# r_series.net
KiCad netlist of a schematic drawn in EAGLE
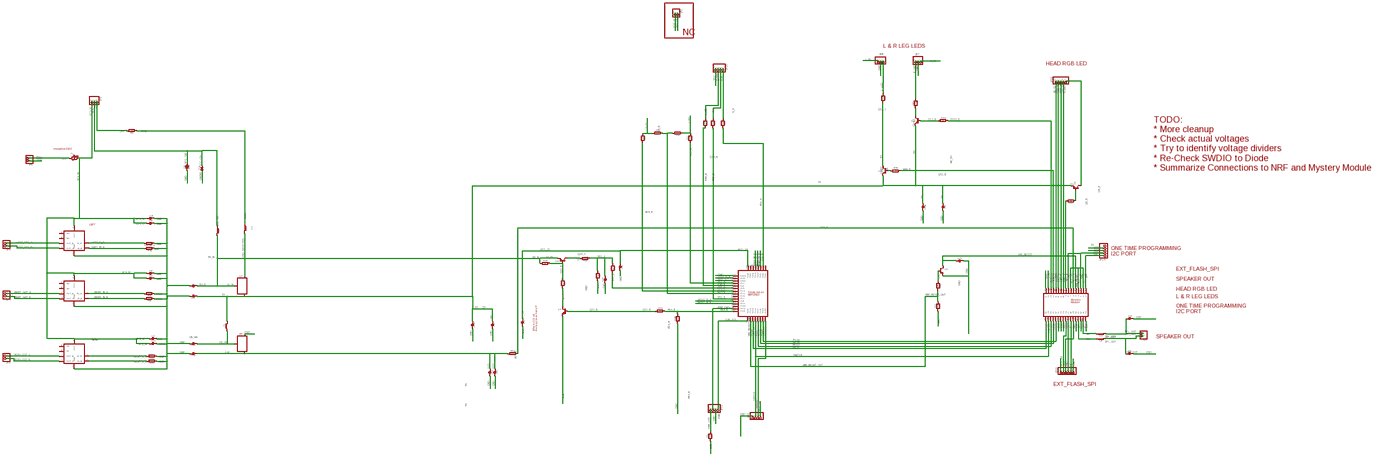
[diagram p0: schematic, sheet 1, overview]
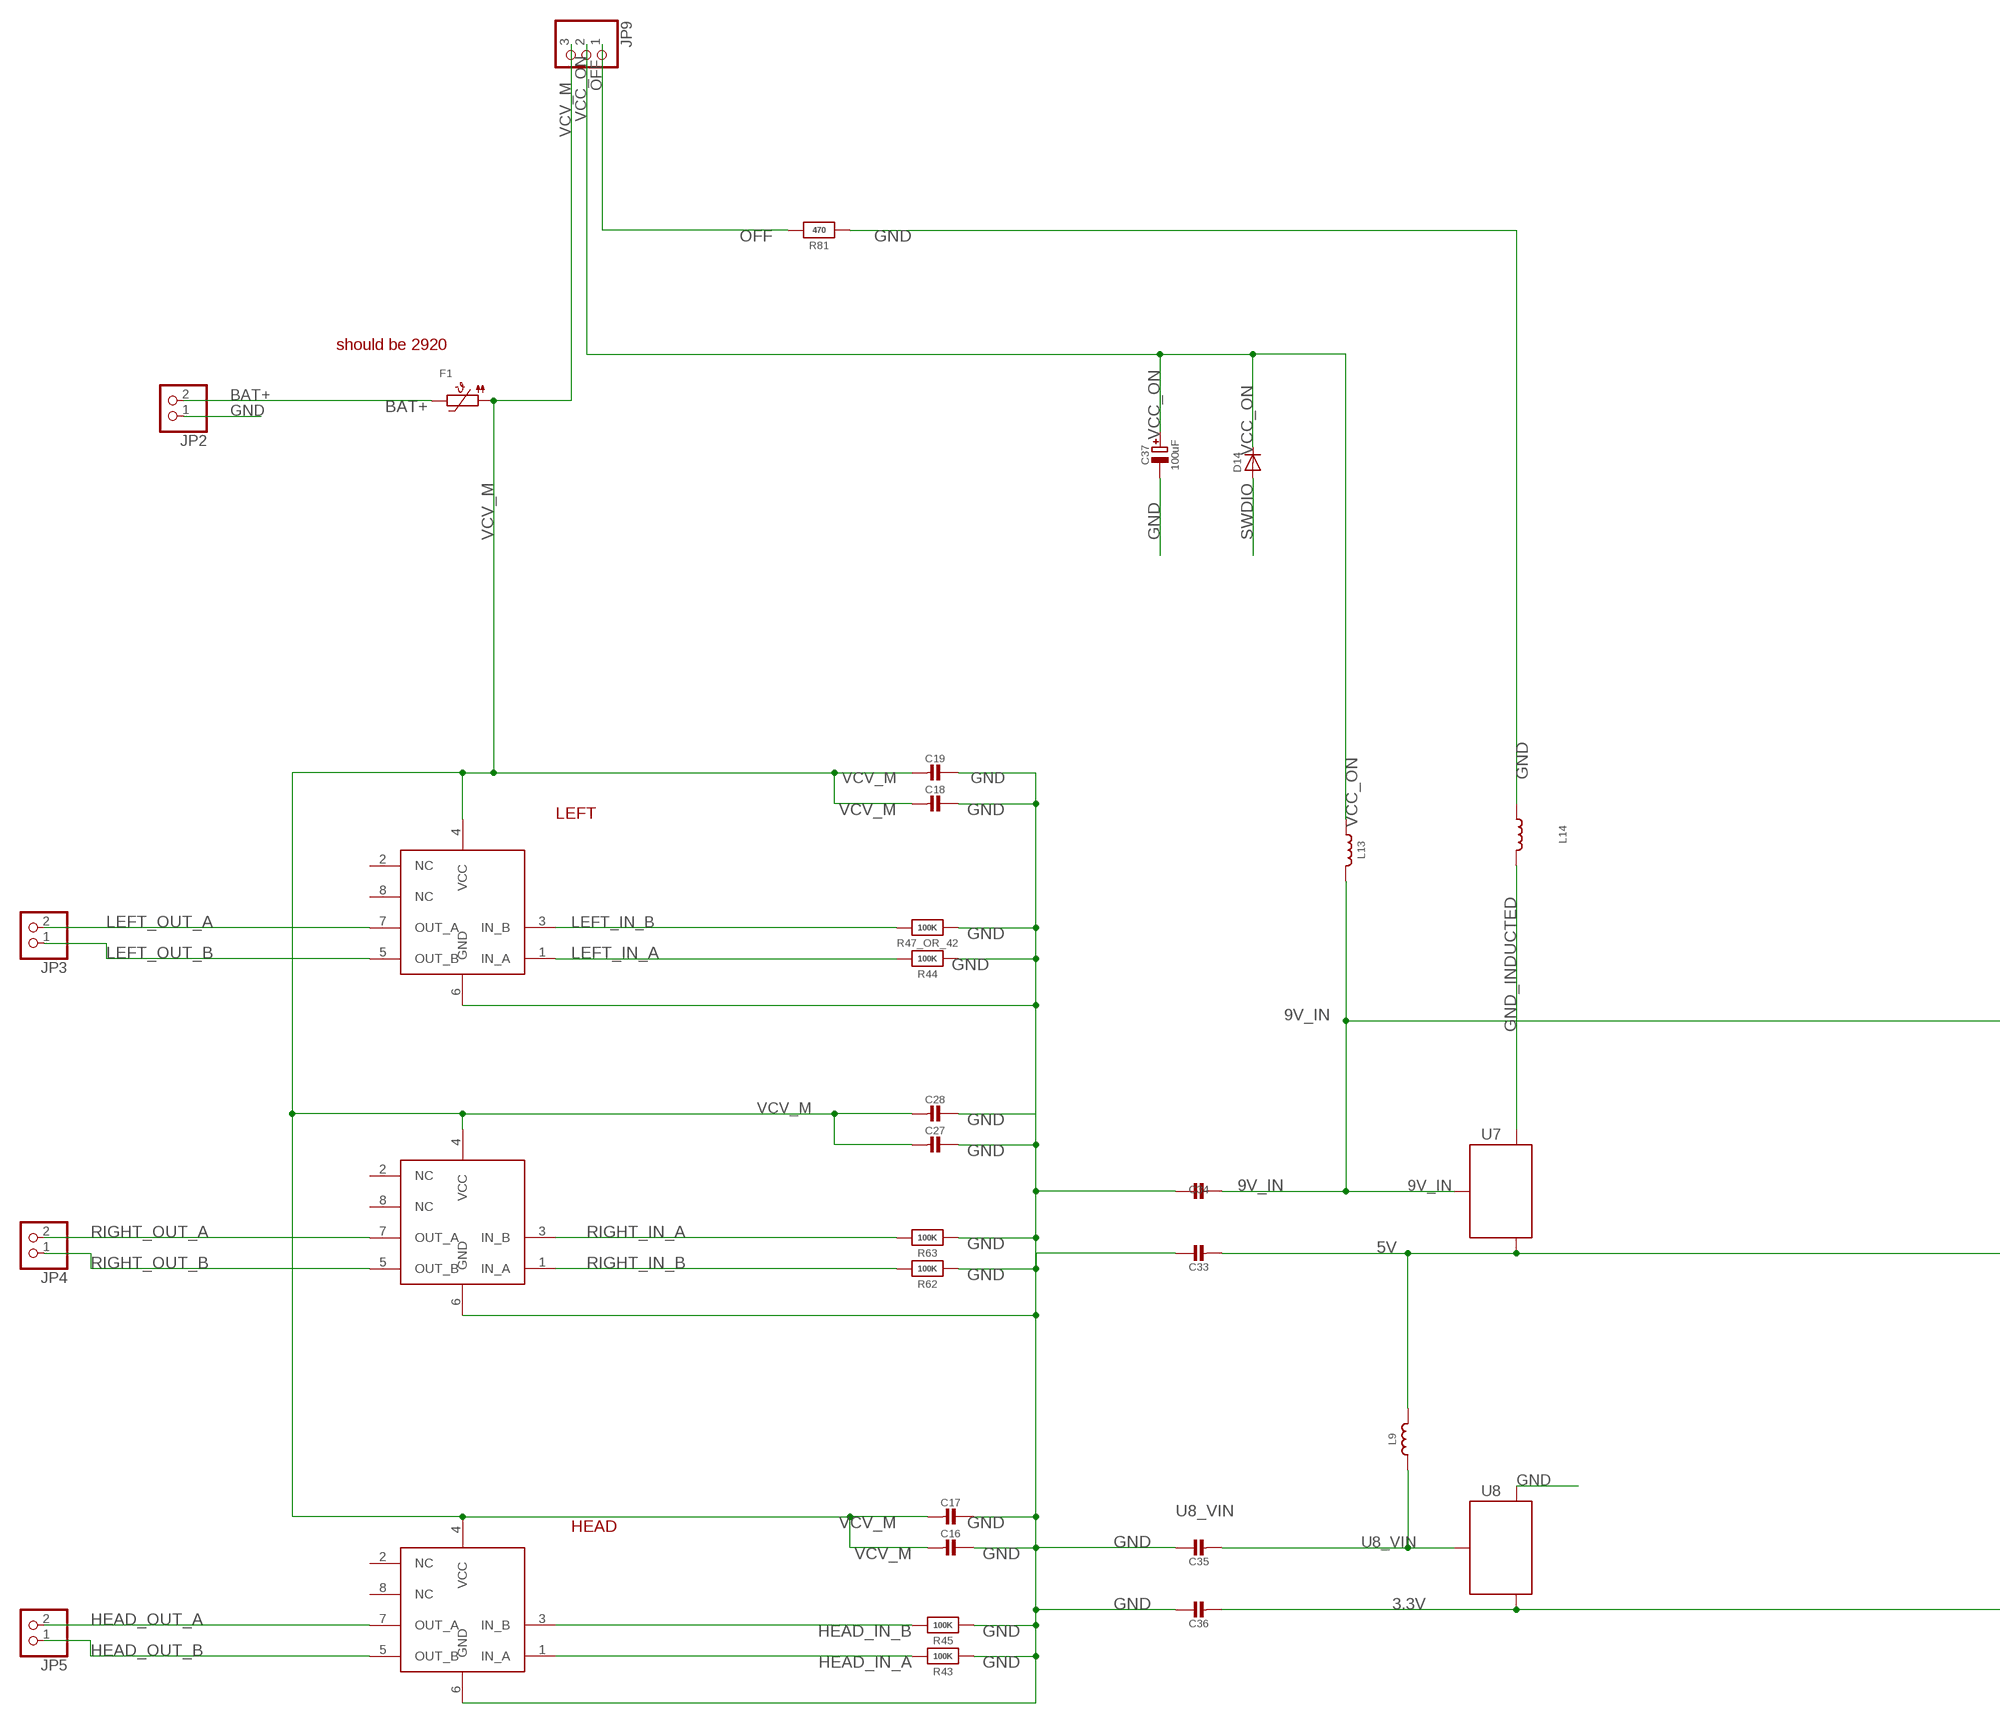
[diagram p1: schematic, sheet 1, part 1 of 4]
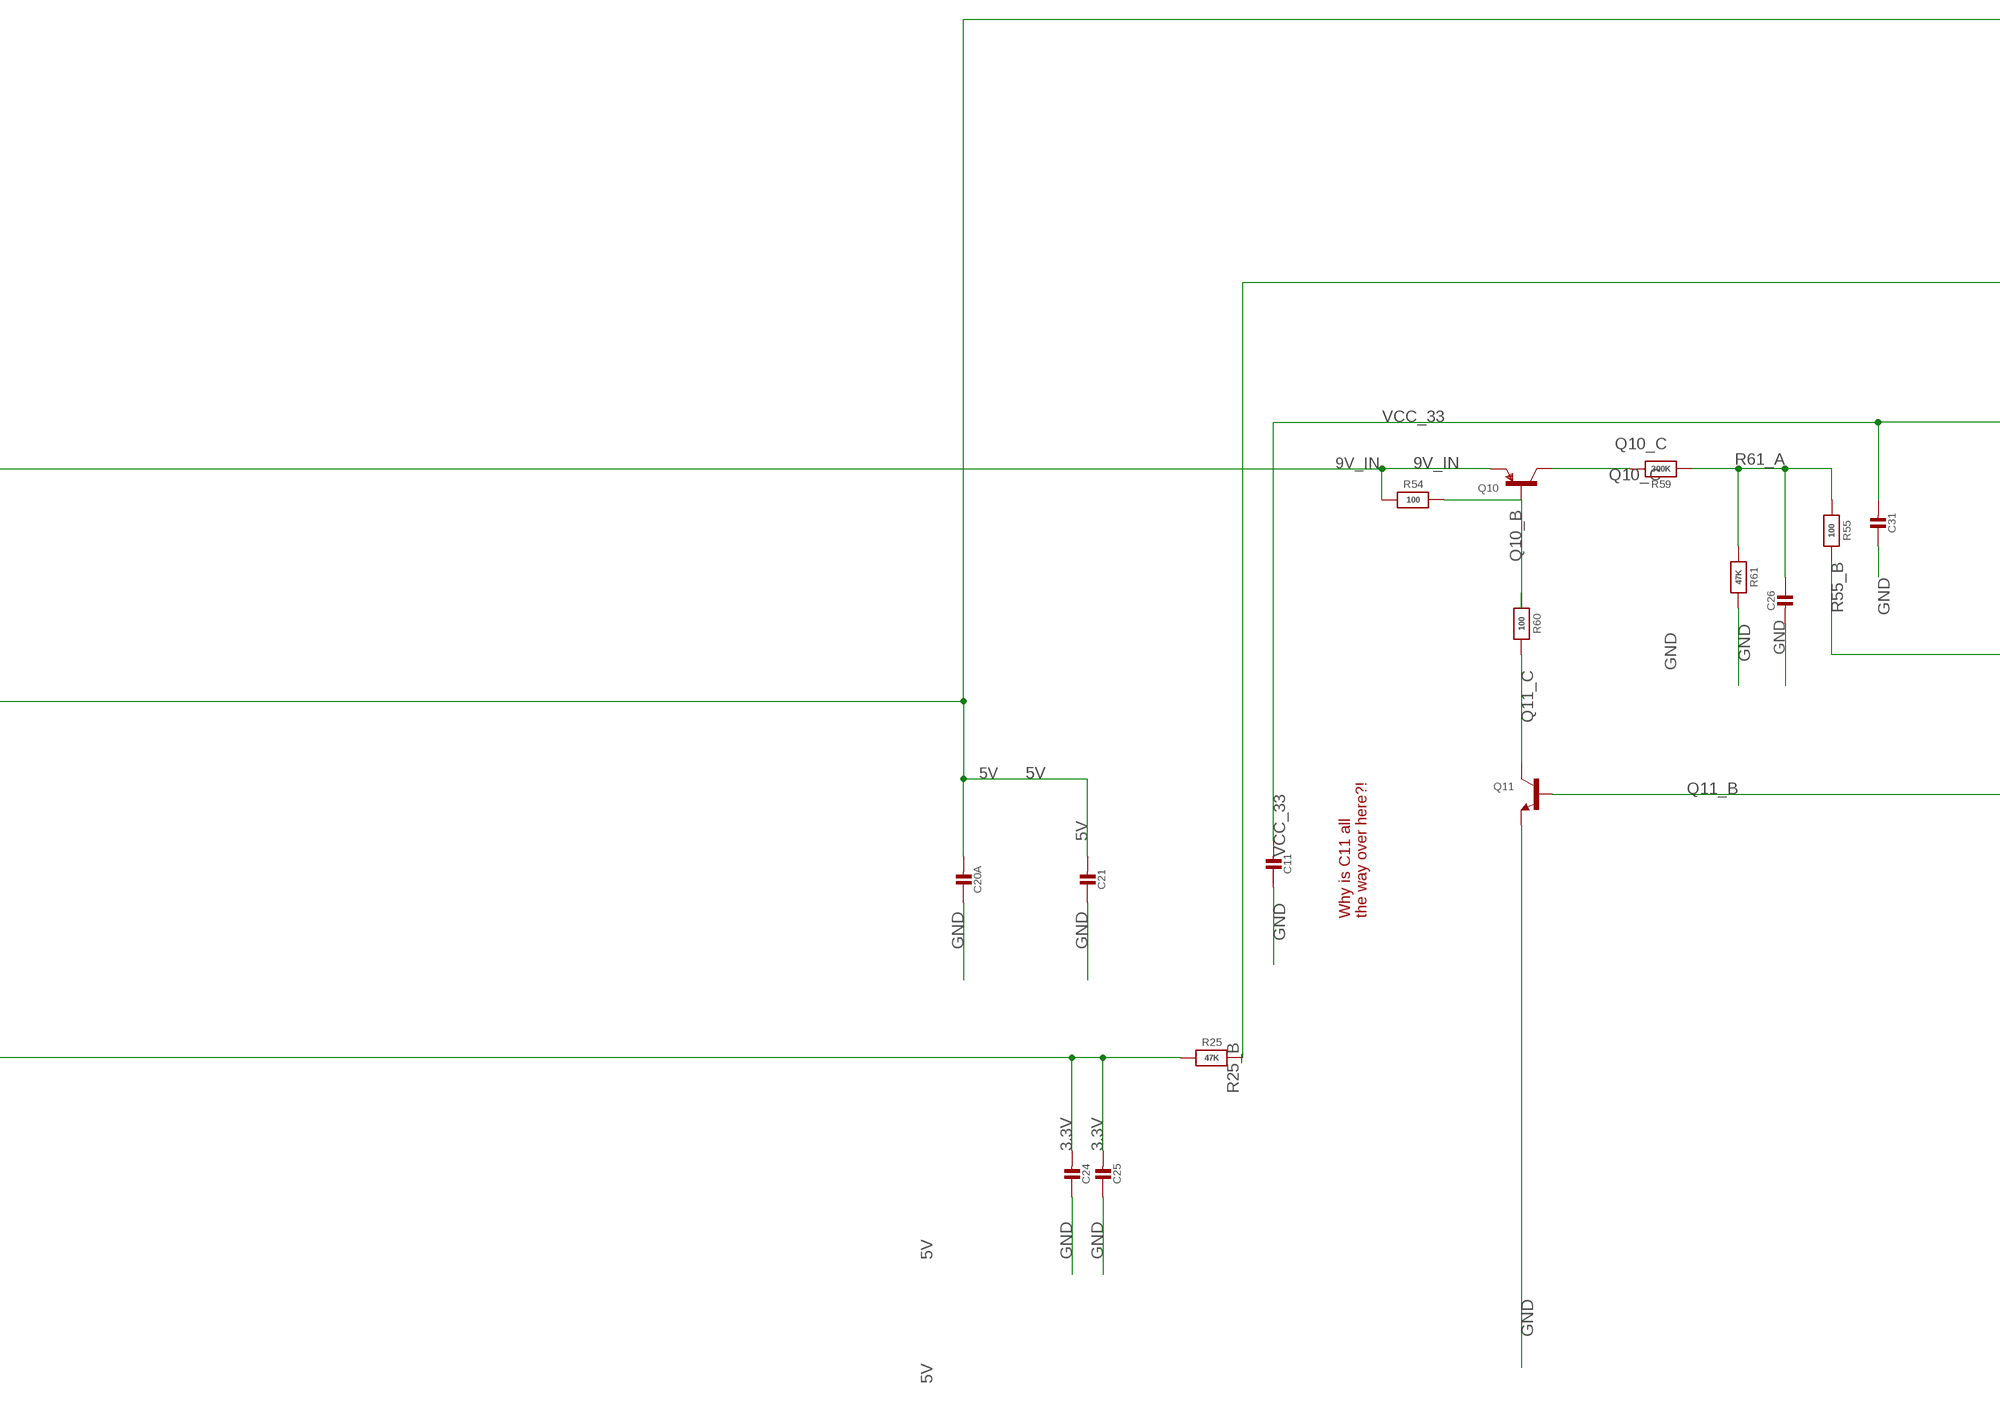
[diagram p2: schematic, sheet 1, part 2 of 4]
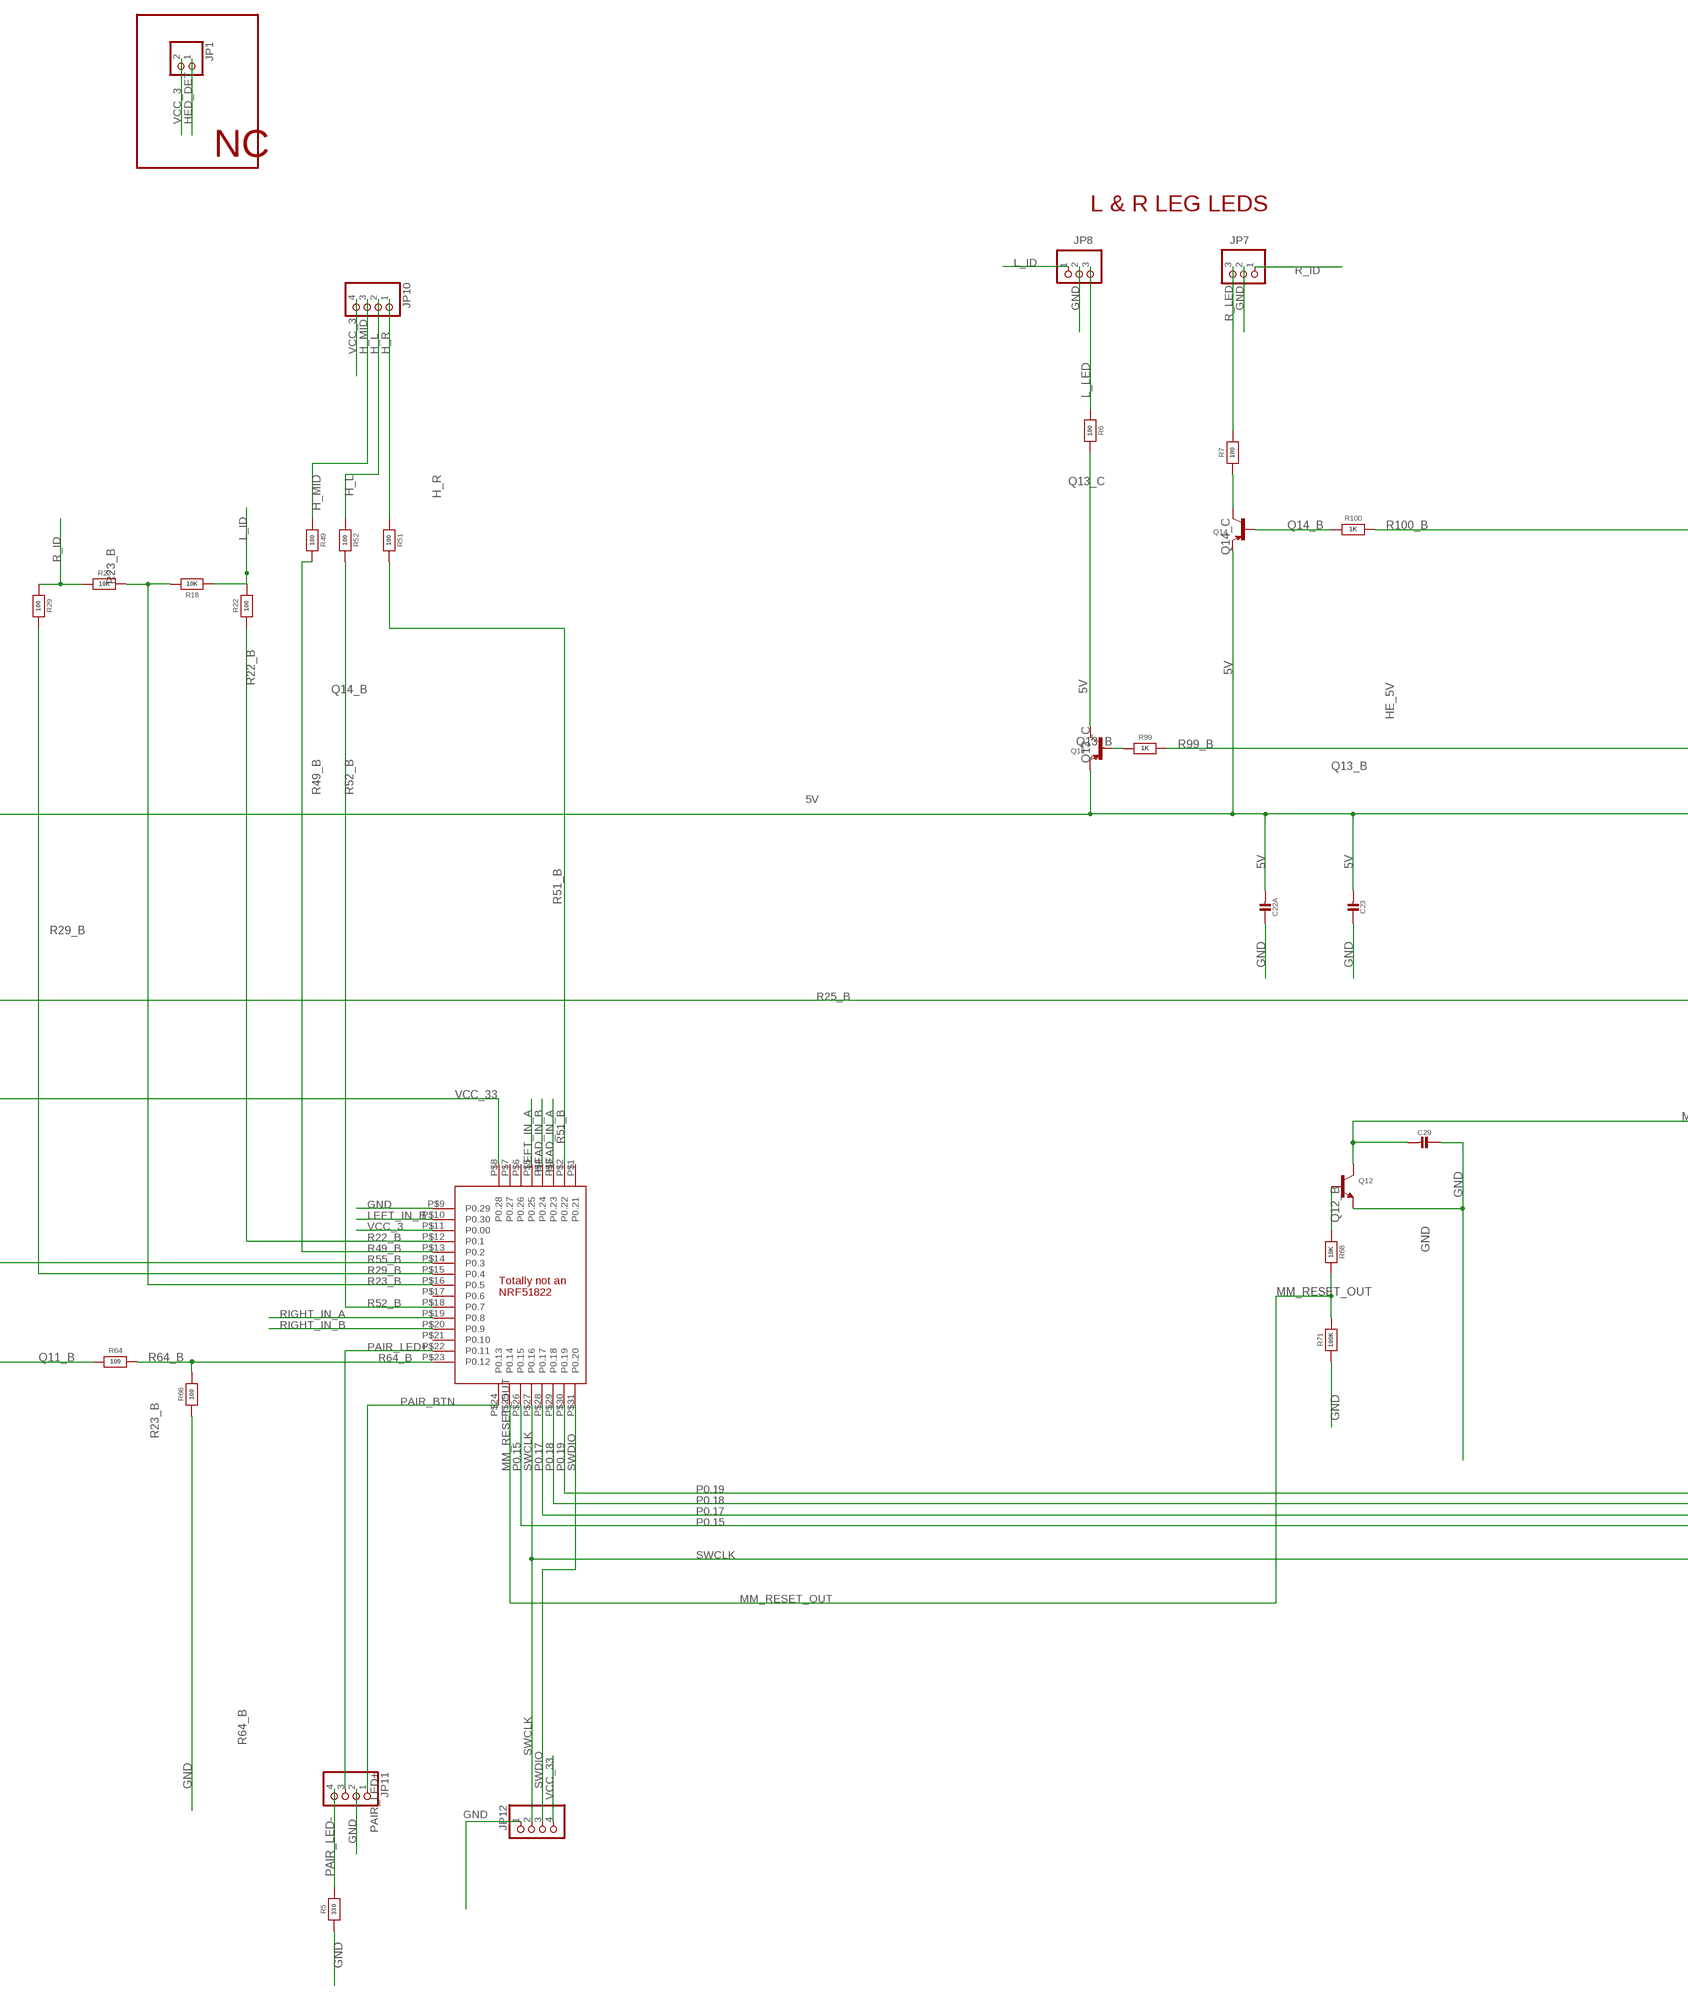
[diagram p3: schematic, sheet 1, part 3 of 4]
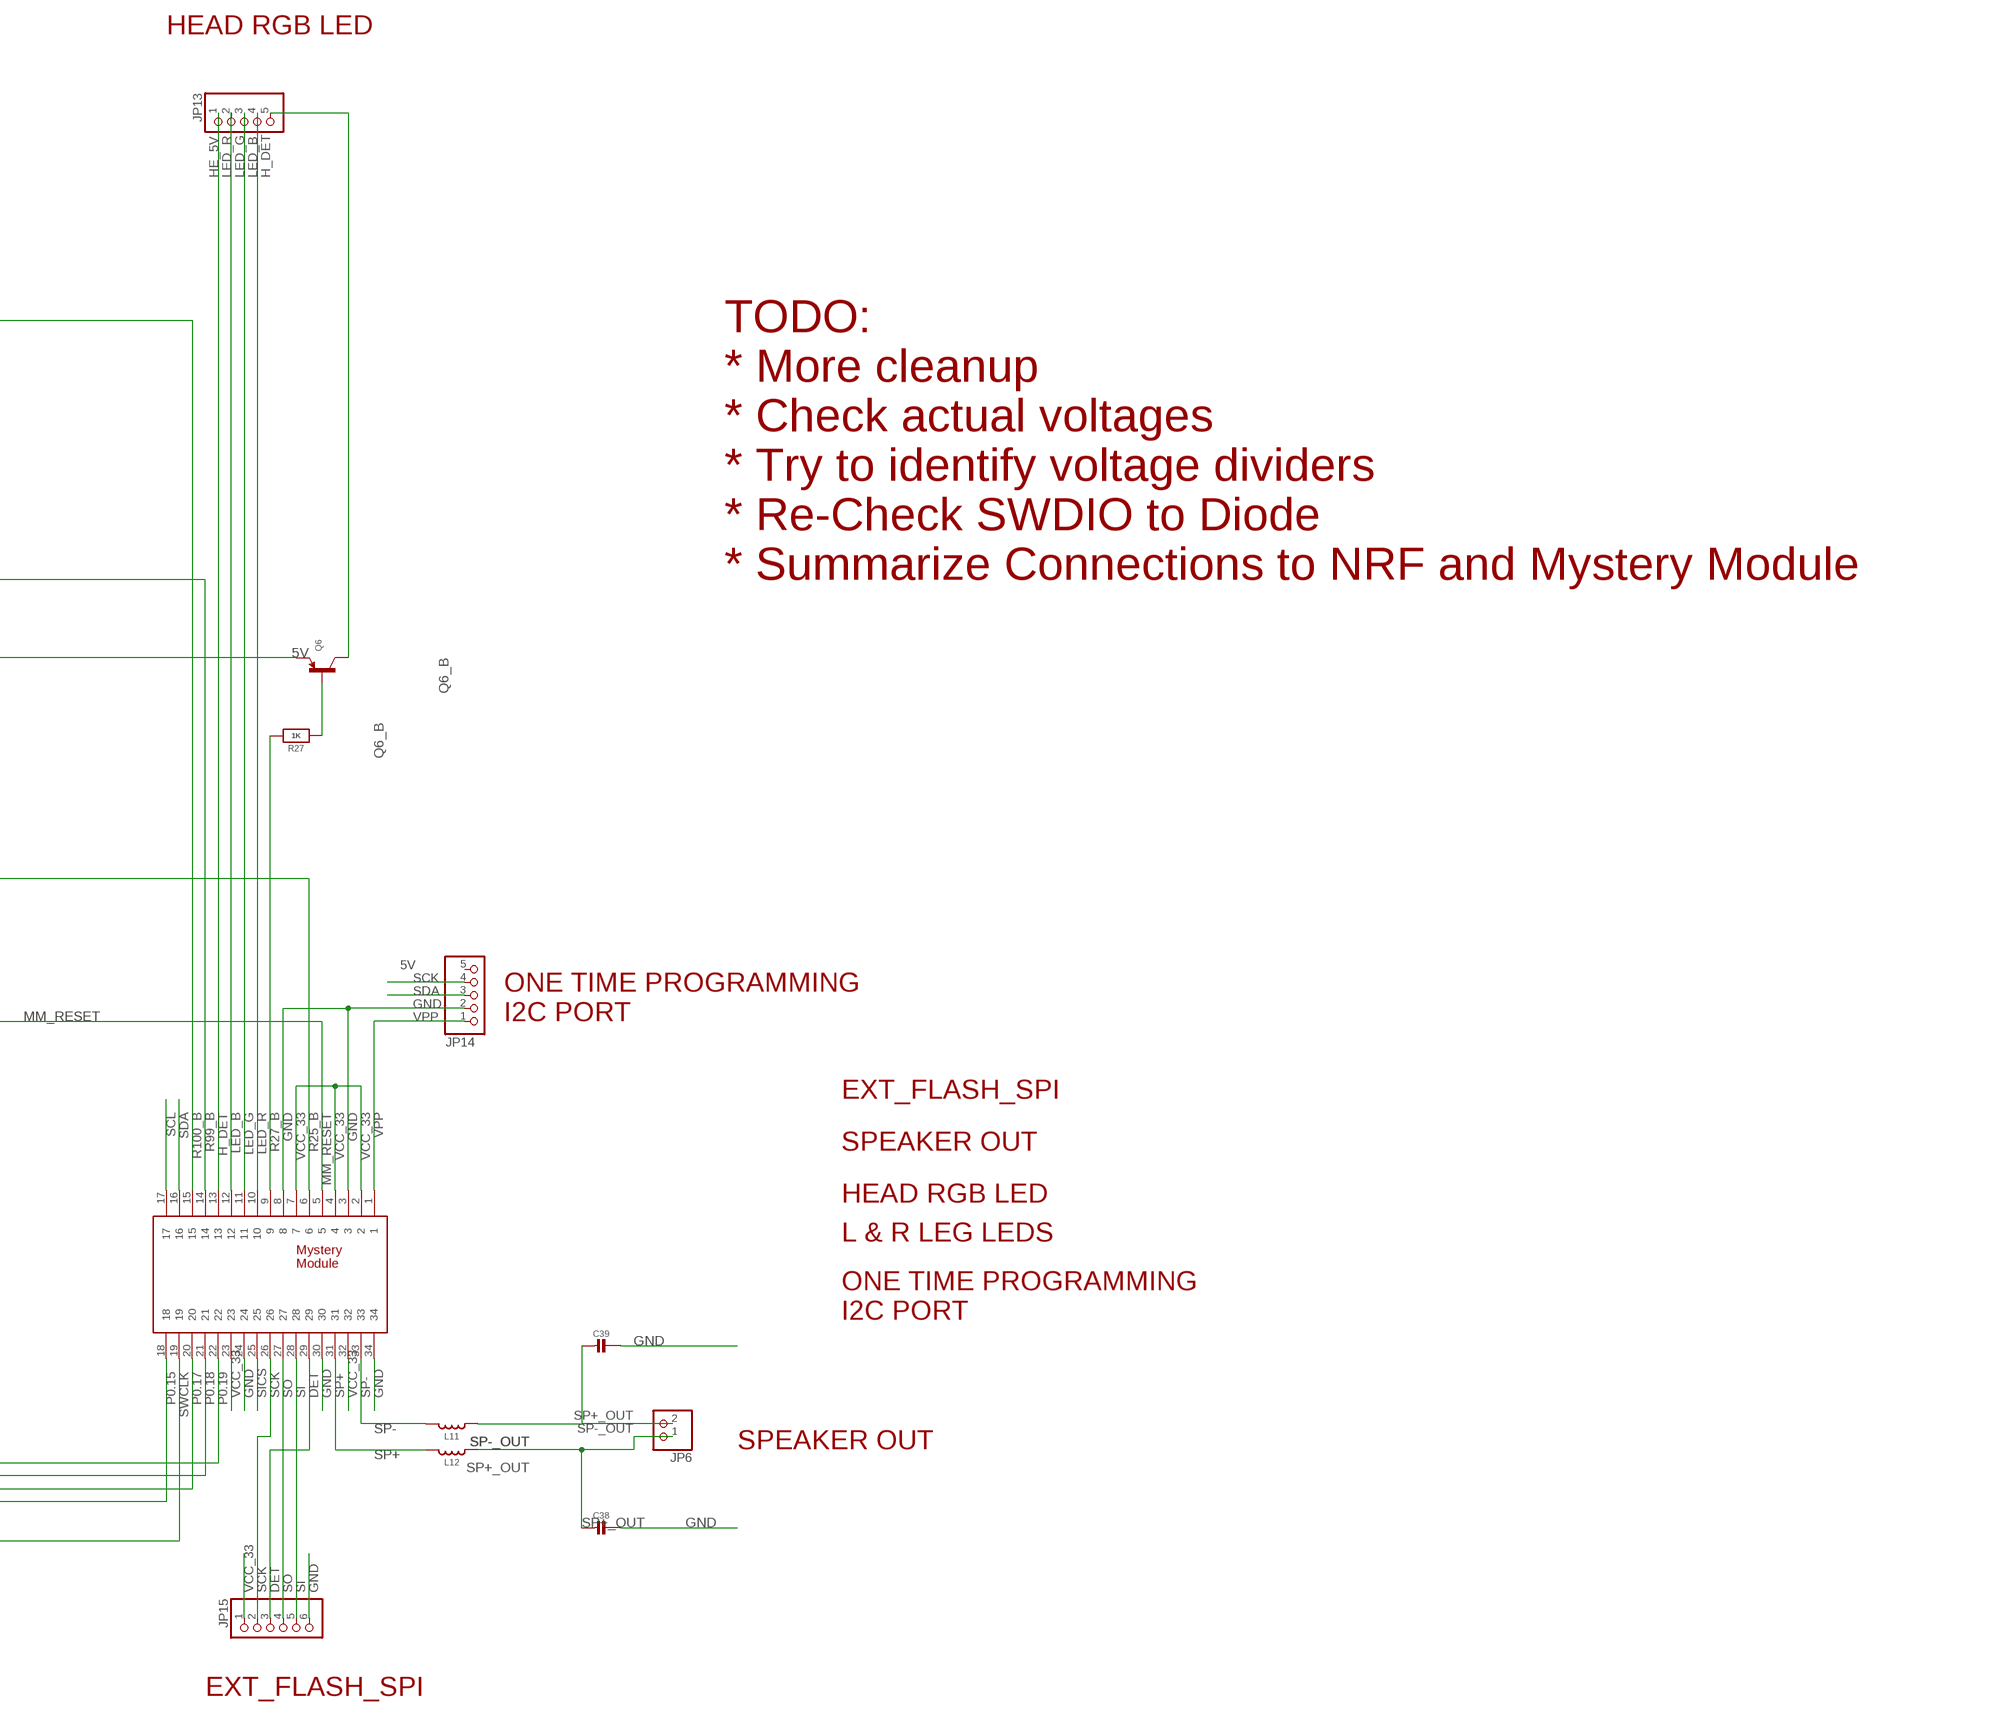
[diagram p4: schematic, sheet 1, part 4 of 4]

(export (version "E")
  (design (tool "Eeschema 10.0.6"))
  (components
    (comp (ref "C11")
      (value "CAP_CERAMIC0603_NO")
      (footprint "eagle-import:0603-NO")
      (libsource (lib "eagle-import") (part "CAP_CERAMIC0603_NO"))
    )
    (comp (ref "C16")
      (value "CAP_CERAMIC0603_NO")
      (footprint "eagle-import:0603-NO")
      (libsource (lib "eagle-import") (part "CAP_CERAMIC0603_NO"))
    )
    (comp (ref "C17")
      (value "CAP_CERAMIC_0805MP")
      (footprint "eagle-import:_0805MP")
      (libsource (lib "eagle-import") (part "CAP_CERAMIC_0805MP"))
    )
    (comp (ref "C18")
      (value "CAP_CERAMIC0603_NO")
      (footprint "eagle-import:0603-NO")
      (libsource (lib "eagle-import") (part "CAP_CERAMIC0603_NO"))
    )
    (comp (ref "C19")
      (value "CAP_CERAMIC_0805MP")
      (footprint "eagle-import:_0805MP")
      (libsource (lib "eagle-import") (part "CAP_CERAMIC_0805MP"))
    )
    (comp (ref "C20A")
      (value "CAP_CERAMIC_0805MP")
      (footprint "eagle-import:_0805MP")
      (libsource (lib "eagle-import") (part "CAP_CERAMIC_0805MP"))
    )
    (comp (ref "C21")
      (value "CAP_CERAMIC0603_NO")
      (footprint "eagle-import:0603-NO")
      (libsource (lib "eagle-import") (part "CAP_CERAMIC0603_NO"))
    )
    (comp (ref "C22A")
      (value "CAP_CERAMIC_0805MP")
      (footprint "eagle-import:_0805MP")
      (libsource (lib "eagle-import") (part "CAP_CERAMIC_0805MP"))
    )
    (comp (ref "C23")
      (value "CAP_CERAMIC0603_NO")
      (footprint "eagle-import:0603-NO")
      (libsource (lib "eagle-import") (part "CAP_CERAMIC0603_NO"))
    )
    (comp (ref "C24")
      (value "CAP_CERAMIC0603_NO")
      (footprint "eagle-import:0603-NO")
      (libsource (lib "eagle-import") (part "CAP_CERAMIC0603_NO"))
    )
    (comp (ref "C25")
      (value "CAP_CERAMIC0603_NO")
      (footprint "eagle-import:0603-NO")
      (libsource (lib "eagle-import") (part "CAP_CERAMIC0603_NO"))
    )
    (comp (ref "C26")
      (value "CAP_CERAMIC0603_NO")
      (footprint "eagle-import:0603-NO")
      (libsource (lib "eagle-import") (part "CAP_CERAMIC0603_NO"))
    )
    (comp (ref "C27")
      (value "CAP_CERAMIC0603_NO")
      (footprint "eagle-import:0603-NO")
      (libsource (lib "eagle-import") (part "CAP_CERAMIC0603_NO"))
    )
    (comp (ref "C28")
      (value "CAP_CERAMIC_0805MP")
      (footprint "eagle-import:_0805MP")
      (libsource (lib "eagle-import") (part "CAP_CERAMIC_0805MP"))
    )
    (comp (ref "C29")
      (value "CAP_CERAMIC0603_NO")
      (footprint "eagle-import:0603-NO")
      (libsource (lib "eagle-import") (part "CAP_CERAMIC0603_NO"))
    )
    (comp (ref "C31")
      (value "CAP_CERAMIC0603_NO")
      (footprint "eagle-import:0603-NO")
      (libsource (lib "eagle-import") (part "CAP_CERAMIC0603_NO"))
    )
    (comp (ref "C33")
      (value "CAP_CERAMIC0603_NO")
      (footprint "eagle-import:0603-NO")
      (libsource (lib "eagle-import") (part "CAP_CERAMIC0603_NO"))
    )
    (comp (ref "C34")
      (value "CAP_CERAMIC0603_NO")
      (footprint "eagle-import:0603-NO")
      (libsource (lib "eagle-import") (part "CAP_CERAMIC0603_NO"))
    )
    (comp (ref "C35")
      (value "CAP_CERAMIC0603_NO")
      (footprint "eagle-import:0603-NO")
      (libsource (lib "eagle-import") (part "CAP_CERAMIC0603_NO"))
    )
    (comp (ref "C36")
      (value "CAP_CERAMIC0603_NO")
      (footprint "eagle-import:0603-NO")
      (libsource (lib "eagle-import") (part "CAP_CERAMIC0603_NO"))
    )
    (comp (ref "C37")
      (value "100uF")
      (footprint "eagle-import:PANASONIC_D")
      (libsource (lib "eagle-import") (part "CAP_ELECTROLYTICPANASONIC_D"))
    )
    (comp (ref "C38")
      (value "CAP_CERAMIC0603_NO")
      (footprint "eagle-import:0603-NO")
      (libsource (lib "eagle-import") (part "CAP_CERAMIC0603_NO"))
    )
    (comp (ref "C39")
      (value "CAP_CERAMIC0603_NO")
      (footprint "eagle-import:0603-NO")
      (libsource (lib "eagle-import") (part "CAP_CERAMIC0603_NO"))
    )
    (comp (ref "D14")
      (value "DIODESOD-323")
      (footprint "eagle-import:SOD-323")
      (libsource (lib "eagle-import") (part "DIODESOD-323"))
    )
    (comp (ref "F1")
      (value "PTC1812")
      (footprint "eagle-import:PTC1812")
      (libsource (lib "eagle-import") (part "PTC1812"))
    )
    (comp (ref "JP1")
      (value "HEADER-1X2ROUND")
      (footprint "eagle-import:1X02_ROUND")
      (libsource (lib "eagle-import") (part "HEADER-1X2ROUND"))
    )
    (comp (ref "JP2")
      (value "HEADER-1X2ROUND")
      (footprint "eagle-import:1X02_ROUND")
      (libsource (lib "eagle-import") (part "HEADER-1X2ROUND"))
    )
    (comp (ref "JP3")
      (value "HEADER-1X2ROUND")
      (footprint "eagle-import:1X02_ROUND")
      (libsource (lib "eagle-import") (part "HEADER-1X2ROUND"))
    )
    (comp (ref "JP4")
      (value "HEADER-1X2ROUND")
      (footprint "eagle-import:1X02_ROUND")
      (libsource (lib "eagle-import") (part "HEADER-1X2ROUND"))
    )
    (comp (ref "JP5")
      (value "HEADER-1X2ROUND")
      (footprint "eagle-import:1X02_ROUND")
      (libsource (lib "eagle-import") (part "HEADER-1X2ROUND"))
    )
    (comp (ref "JP6")
      (value "HEADER-1X2ROUND")
      (footprint "eagle-import:1X02_ROUND")
      (libsource (lib "eagle-import") (part "HEADER-1X2ROUND"))
    )
    (comp (ref "JP7")
      (value "HEADER-1X3ROUND")
      (footprint "eagle-import:1X03_ROUND")
      (libsource (lib "eagle-import") (part "HEADER-1X3ROUND"))
    )
    (comp (ref "JP8")
      (value "HEADER-1X3ROUND")
      (footprint "eagle-import:1X03_ROUND")
      (libsource (lib "eagle-import") (part "HEADER-1X3ROUND"))
    )
    (comp (ref "JP9")
      (value "HEADER-1X3ROUND")
      (footprint "eagle-import:1X03_ROUND")
      (libsource (lib "eagle-import") (part "HEADER-1X3ROUND"))
    )
    (comp (ref "JP10")
      (value "HEADER-1X4ROUND")
      (footprint "eagle-import:1X04_ROUND")
      (libsource (lib "eagle-import") (part "HEADER-1X4ROUND"))
    )
    (comp (ref "JP11")
      (value "HEADER-1X4ROUND")
      (footprint "eagle-import:1X04_ROUND")
      (libsource (lib "eagle-import") (part "HEADER-1X4ROUND"))
    )
    (comp (ref "JP12")
      (value "HEADER-1X4ROUND")
      (footprint "eagle-import:1X04_ROUND")
      (libsource (lib "eagle-import") (part "HEADER-1X4ROUND"))
    )
    (comp (ref "JP13")
      (value "HEADER-1X5ROUND")
      (footprint "eagle-import:1X05_ROUND")
      (libsource (lib "eagle-import") (part "HEADER-1X5ROUND"))
    )
    (comp (ref "JP14")
      (value "HEADER-1X5ROUND")
      (footprint "eagle-import:1X05_ROUND")
      (libsource (lib "eagle-import") (part "HEADER-1X5ROUND"))
    )
    (comp (ref "JP15")
      (value "HEADER-1X6ROUND")
      (footprint "eagle-import:1X06_ROUND")
      (libsource (lib "eagle-import") (part "HEADER-1X6ROUND"))
    )
    (comp (ref "L9")
      (value "INDUCTOR0805-NO")
      (footprint "eagle-import:0805-NO")
      (libsource (lib "eagle-import") (part "INDUCTOR0805-NO"))
    )
    (comp (ref "L11")
      (value "INDUCTOR0603_NO")
      (footprint "eagle-import:0603-NO")
      (libsource (lib "eagle-import") (part "INDUCTOR0603_NO"))
    )
    (comp (ref "L12")
      (value "INDUCTOR0603_NO")
      (footprint "eagle-import:0603-NO")
      (libsource (lib "eagle-import") (part "INDUCTOR0603_NO"))
    )
    (comp (ref "L13")
      (value "INDUCTOR0805-NO")
      (footprint "eagle-import:0805-NO")
      (libsource (lib "eagle-import") (part "INDUCTOR0805-NO"))
    )
    (comp (ref "L14")
      (value "INDUCTOR0805-NO")
      (footprint "eagle-import:0805-NO")
      (libsource (lib "eagle-import") (part "INDUCTOR0805-NO"))
    )
    (comp (ref "Q6")
      (value "TRANSISTOR_PNPSOT23-REFLOW")
      (footprint "eagle-import:SOT23-R")
      (libsource (lib "eagle-import") (part "TRANSISTOR_PNPSOT23-REFLOW"))
    )
    (comp (ref "Q10")
      (value "TRANSISTOR_PNPSOT23-REFLOW")
      (footprint "eagle-import:SOT23-R")
      (libsource (lib "eagle-import") (part "TRANSISTOR_PNPSOT23-REFLOW"))
    )
    (comp (ref "Q11")
      (value "TRANSISTOR_NPNWIDE")
      (footprint "eagle-import:SOT23-WIDE")
      (libsource (lib "eagle-import") (part "TRANSISTOR_NPNWIDE"))
    )
    (comp (ref "Q12")
      (value "TRANSISTOR_NPNWIDE")
      (footprint "eagle-import:SOT23-WIDE")
      (libsource (lib "eagle-import") (part "TRANSISTOR_NPNWIDE"))
    )
    (comp (ref "Q13")
      (value "TRANSISTOR_PNPSOT23-REFLOW")
      (footprint "eagle-import:SOT23-R")
      (libsource (lib "eagle-import") (part "TRANSISTOR_PNPSOT23-REFLOW"))
    )
    (comp (ref "Q14")
      (value "TRANSISTOR_PNPSOT23-REFLOW")
      (footprint "eagle-import:SOT23-R")
      (libsource (lib "eagle-import") (part "TRANSISTOR_PNPSOT23-REFLOW"))
    )
    (comp (ref "R5")
      (value "330")
      (footprint "eagle-import:0603-NO")
      (libsource (lib "eagle-import") (part "RESISTOR_0603_NOOUT"))
    )
    (comp (ref "R6")
      (value "100")
      (footprint "eagle-import:0603-NO")
      (libsource (lib "eagle-import") (part "RESISTOR_0603_NOOUT"))
    )
    (comp (ref "R7")
      (value "100")
      (footprint "eagle-import:0603-NO")
      (libsource (lib "eagle-import") (part "RESISTOR_0603_NOOUT"))
    )
    (comp (ref "R18")
      (value "10K")
      (footprint "eagle-import:0603-NO")
      (libsource (lib "eagle-import") (part "RESISTOR_0603_NOOUT"))
    )
    (comp (ref "R22")
      (value "100")
      (footprint "eagle-import:0603-NO")
      (libsource (lib "eagle-import") (part "RESISTOR_0603_NOOUT"))
    )
    (comp (ref "R23")
      (value "10K")
      (footprint "eagle-import:0603-NO")
      (libsource (lib "eagle-import") (part "RESISTOR_0603_NOOUT"))
    )
    (comp (ref "R25")
      (value "47K")
      (footprint "eagle-import:0603-NO")
      (libsource (lib "eagle-import") (part "RESISTOR_0603_NOOUT"))
    )
    (comp (ref "R27")
      (value "1K")
      (footprint "eagle-import:0603-NO")
      (libsource (lib "eagle-import") (part "RESISTOR_0603_NOOUT"))
    )
    (comp (ref "R29")
      (value "100")
      (footprint "eagle-import:0603-NO")
      (libsource (lib "eagle-import") (part "RESISTOR_0603_NOOUT"))
    )
    (comp (ref "R43")
      (value "100K")
      (footprint "eagle-import:0603-NO")
      (libsource (lib "eagle-import") (part "RESISTOR_0603_NOOUT"))
    )
    (comp (ref "R44")
      (value "100K")
      (footprint "eagle-import:0603-NO")
      (libsource (lib "eagle-import") (part "RESISTOR_0603_NOOUT"))
    )
    (comp (ref "R45")
      (value "100K")
      (footprint "eagle-import:0603-NO")
      (libsource (lib "eagle-import") (part "RESISTOR_0603_NOOUT"))
    )
    (comp (ref "R47_OR_42")
      (value "100K")
      (footprint "eagle-import:0603-NO")
      (libsource (lib "eagle-import") (part "RESISTOR_0603_NOOUT"))
    )
    (comp (ref "R49")
      (value "100")
      (footprint "eagle-import:0603-NO")
      (libsource (lib "eagle-import") (part "RESISTOR_0603_NOOUT"))
    )
    (comp (ref "R51")
      (value "100")
      (footprint "eagle-import:0603-NO")
      (libsource (lib "eagle-import") (part "RESISTOR_0603_NOOUT"))
    )
    (comp (ref "R52")
      (value "100")
      (footprint "eagle-import:0603-NO")
      (libsource (lib "eagle-import") (part "RESISTOR_0603_NOOUT"))
    )
    (comp (ref "R54")
      (value "100")
      (footprint "eagle-import:0603-NO")
      (libsource (lib "eagle-import") (part "RESISTOR_0603_NOOUT"))
    )
    (comp (ref "R55")
      (value "100")
      (footprint "eagle-import:0603-NO")
      (libsource (lib "eagle-import") (part "RESISTOR_0603_NOOUT"))
    )
    (comp (ref "R59")
      (value "300K")
      (footprint "eagle-import:0603-NO")
      (libsource (lib "eagle-import") (part "RESISTOR_0603_NOOUT"))
    )
    (comp (ref "R60")
      (value "100")
      (footprint "eagle-import:0603-NO")
      (libsource (lib "eagle-import") (part "RESISTOR_0603_NOOUT"))
    )
    (comp (ref "R61")
      (value "47K")
      (footprint "eagle-import:0603-NO")
      (libsource (lib "eagle-import") (part "RESISTOR_0603_NOOUT"))
    )
    (comp (ref "R62")
      (value "100K")
      (footprint "eagle-import:0603-NO")
      (libsource (lib "eagle-import") (part "RESISTOR_0603_NOOUT"))
    )
    (comp (ref "R63")
      (value "100K")
      (footprint "eagle-import:0603-NO")
      (libsource (lib "eagle-import") (part "RESISTOR_0603_NOOUT"))
    )
    (comp (ref "R64")
      (value "100")
      (footprint "eagle-import:0603-NO")
      (libsource (lib "eagle-import") (part "RESISTOR_0603_NOOUT"))
    )
    (comp (ref "R66")
      (value "100")
      (footprint "eagle-import:0603-NO")
      (libsource (lib "eagle-import") (part "RESISTOR_0603_NOOUT"))
    )
    (comp (ref "R68")
      (value "10K")
      (footprint "eagle-import:0603-NO")
      (libsource (lib "eagle-import") (part "RESISTOR_0603_NOOUT"))
    )
    (comp (ref "R71")
      (value "100K")
      (footprint "eagle-import:0603-NO")
      (libsource (lib "eagle-import") (part "RESISTOR_0603_NOOUT"))
    )
    (comp (ref "R81")
      (value "470")
      (footprint "eagle-import:_0805MP")
      (libsource (lib "eagle-import") (part "RESISTOR_0805MP"))
    )
    (comp (ref "R99")
      (value "1K")
      (footprint "eagle-import:0603-NO")
      (libsource (lib "eagle-import") (part "RESISTOR_0603_NOOUT"))
    )
    (comp (ref "R100")
      (value "1K")
      (footprint "eagle-import:0603-NO")
      (libsource (lib "eagle-import") (part "RESISTOR_0603_NOOUT"))
    )
    (comp (ref "U$1")
      (value "AM1037A")
      (footprint "eagle-import:SOIC8_208MIL")
      (libsource (lib "eagle-import") (part "AM1037A"))
    )
    (comp (ref "U$2")
      (value "AM1037A")
      (footprint "eagle-import:SOIC8_208MIL")
      (libsource (lib "eagle-import") (part "AM1037A"))
    )
    (comp (ref "U$3")
      (value "AM1037A")
      (footprint "eagle-import:SOIC8_208MIL")
      (libsource (lib "eagle-import") (part "AM1037A"))
    )
    (comp (ref "U$4")
      (value "KNRF51822_A24")
      (footprint "eagle-import:KNRF51822")
      (libsource (lib "eagle-import") (part "KNRF51822_A24"))
    )
    (comp (ref "U$5")
      (value "GPCD9TP340A_DROID")
      (footprint "eagle-import:GPCD9TP340A")
      (libsource (lib "eagle-import") (part "GPCD9TP340A_DROID"))
    )
    (comp (ref "U7")
      (value "ME62XX")
      (footprint "eagle-import:SOT89")
      (fields (field (name "MPN") "2DB1713-13"))
      (libsource (lib "eagle-import") (part "ME62XX"))
    )
    (comp (ref "U8")
      (value "ME62XX")
      (footprint "eagle-import:SOT89")
      (fields (field (name "MPN") "2DB1713-13"))
      (libsource (lib "eagle-import") (part "ME62XX"))
    )
  )
  (nets
    (net (code "1") (name "/3.3V") (class "Default")
      (node (ref "C24") (pin "2") (pinfunction "2_2") (pintype "passive"))
      (node (ref "C25") (pin "2") (pinfunction "2_2") (pintype "passive"))
      (node (ref "C36") (pin "2") (pinfunction "2_2") (pintype "passive"))
      (node (ref "R25") (pin "1") (pinfunction "1_1") (pintype "passive"))
      (node (ref "U8") (pin "2") (pinfunction "VOUT_2") (pintype "passive"))
      (node (ref "U8") (pin "2@1") (pinfunction "VOUT_2@1") (pintype "passive"))
    )
    (net (code "2") (name "/5V") (class "Default")
      (node (ref "C20A") (pin "2") (pinfunction "2_2") (pintype "passive"))
      (node (ref "C21") (pin "2") (pinfunction "2_2") (pintype "passive"))
      (node (ref "C22A") (pin "2") (pinfunction "2_2") (pintype "passive"))
      (node (ref "C23") (pin "2") (pinfunction "2_2") (pintype "passive"))
      (node (ref "C33") (pin "2") (pinfunction "2_2") (pintype "passive"))
      (node (ref "L9") (pin "2") (pinfunction "2_2") (pintype "passive"))
      (node (ref "Q13") (pin "2") (pinfunction "E_2") (pintype "passive"))
      (node (ref "Q14") (pin "2") (pinfunction "E_2") (pintype "passive"))
      (node (ref "Q6") (pin "2") (pinfunction "E_2") (pintype "passive"))
      (node (ref "U7") (pin "2") (pinfunction "VOUT_2") (pintype "passive"))
      (node (ref "U7") (pin "2@1") (pinfunction "VOUT_2@1") (pintype "passive"))
    )
    (net (code "3") (name "/9V_IN") (class "Default")
      (node (ref "C34") (pin "2") (pinfunction "2_2") (pintype "passive"))
      (node (ref "L13") (pin "2") (pinfunction "2_2") (pintype "passive"))
      (node (ref "Q10") (pin "2") (pinfunction "E_2") (pintype "passive"))
      (node (ref "R54") (pin "1") (pinfunction "1_1") (pintype "passive"))
      (node (ref "U7") (pin "1") (pinfunction "VSS_1") (pintype "passive"))
    )
    (net (code "4") (name "/BAT+") (class "Default")
      (node (ref "F1") (pin "P$2") (pinfunction "2_P$2") (pintype "passive"))
      (node (ref "JP2") (pin "2") (pinfunction "2_2") (pintype "passive"))
    )
    (net (code "5") (name "/DET") (class "Default")
      (node (ref "JP15") (pin "3") (pinfunction "3_3") (pintype "passive"))
      (node (ref "U$5") (pin "29") (pinfunction "29_29") (pintype "bidirectional"))
    )
    (net (code "6") (name "/GND") (class "Default")
      (node (ref "C11") (pin "1") (pinfunction "1_1") (pintype "passive"))
      (node (ref "C16") (pin "1") (pinfunction "1_1") (pintype "passive"))
      (node (ref "C17") (pin "1") (pinfunction "1_1") (pintype "passive"))
      (node (ref "C18") (pin "1") (pinfunction "1_1") (pintype "passive"))
      (node (ref "C19") (pin "1") (pinfunction "1_1") (pintype "passive"))
      (node (ref "C20A") (pin "1") (pinfunction "1_1") (pintype "passive"))
      (node (ref "C21") (pin "1") (pinfunction "1_1") (pintype "passive"))
      (node (ref "C22A") (pin "1") (pinfunction "1_1") (pintype "passive"))
      (node (ref "C23") (pin "1") (pinfunction "1_1") (pintype "passive"))
      (node (ref "C24") (pin "1") (pinfunction "1_1") (pintype "passive"))
      (node (ref "C25") (pin "1") (pinfunction "1_1") (pintype "passive"))
      (node (ref "C26") (pin "2") (pinfunction "2_2") (pintype "passive"))
      (node (ref "C27") (pin "1") (pinfunction "1_1") (pintype "passive"))
      (node (ref "C28") (pin "1") (pinfunction "1_1") (pintype "passive"))
      (node (ref "C29") (pin "1") (pinfunction "1_1") (pintype "passive"))
      (node (ref "C31") (pin "1") (pinfunction "1_1") (pintype "passive"))
      (node (ref "C33") (pin "1") (pinfunction "1_1") (pintype "passive"))
      (node (ref "C34") (pin "1") (pinfunction "1_1") (pintype "passive"))
      (node (ref "C35") (pin "1") (pinfunction "1_1") (pintype "passive"))
      (node (ref "C36") (pin "1") (pinfunction "1_1") (pintype "passive"))
      (node (ref "C37") (pin "-") (pinfunction "-_-") (pintype "passive"))
      (node (ref "C38") (pin "1") (pinfunction "1_1") (pintype "passive"))
      (node (ref "C39") (pin "1") (pinfunction "1_1") (pintype "passive"))
      (node (ref "JP11") (pin "2") (pinfunction "2_2") (pintype "passive"))
      (node (ref "JP12") (pin "1") (pinfunction "1_1") (pintype "passive"))
      (node (ref "JP14") (pin "2") (pinfunction "2_2") (pintype "passive"))
      (node (ref "JP15") (pin "6") (pinfunction "6_6") (pintype "passive"))
      (node (ref "JP2") (pin "1") (pinfunction "1_1") (pintype "passive"))
      (node (ref "JP7") (pin "2") (pinfunction "2_2") (pintype "passive"))
      (node (ref "JP8") (pin "2") (pinfunction "2_2") (pintype "passive"))
      (node (ref "L14") (pin "1") (pinfunction "1_1") (pintype "passive"))
      (node (ref "Q11") (pin "2") (pinfunction "E_2") (pintype "passive"))
      (node (ref "Q12") (pin "2") (pinfunction "E_2") (pintype "passive"))
      (node (ref "R43") (pin "1") (pinfunction "1_1") (pintype "passive"))
      (node (ref "R44") (pin "1") (pinfunction "1_1") (pintype "passive"))
      (node (ref "R45") (pin "1") (pinfunction "1_1") (pintype "passive"))
      (node (ref "R47_OR_42") (pin "1") (pinfunction "1_1") (pintype "passive"))
      (node (ref "R5") (pin "1") (pinfunction "1_1") (pintype "passive"))
      (node (ref "R61") (pin "2") (pinfunction "2_2") (pintype "passive"))
      (node (ref "R62") (pin "1") (pinfunction "1_1") (pintype "passive"))
      (node (ref "R63") (pin "1") (pinfunction "1_1") (pintype "passive"))
      (node (ref "R66") (pin "1") (pinfunction "1_1") (pintype "passive"))
      (node (ref "R71") (pin "1") (pinfunction "1_1") (pintype "passive"))
      (node (ref "R81") (pin "1") (pinfunction "1_1") (pintype "passive"))
      (node (ref "U$1") (pin "6") (pinfunction "GND_6") (pintype "power_in"))
      (node (ref "U$2") (pin "6") (pinfunction "GND_6") (pintype "power_in"))
      (node (ref "U$3") (pin "6") (pinfunction "GND_6") (pintype "power_in"))
      (node (ref "U$4") (pin "P$9") (pinfunction "P0.29_P$9") (pintype "bidirectional"))
      (node (ref "U$5") (pin "24") (pinfunction "24_24") (pintype "bidirectional"))
      (node (ref "U$5") (pin "3") (pinfunction "3_3") (pintype "bidirectional"))
      (node (ref "U$5") (pin "30") (pinfunction "30_30") (pintype "bidirectional"))
      (node (ref "U$5") (pin "34") (pinfunction "34_34") (pintype "bidirectional"))
      (node (ref "U$5") (pin "8") (pinfunction "8_8") (pintype "bidirectional"))
      (node (ref "U8") (pin "3") (pinfunction "VIN_3") (pintype "passive"))
    )
    (net (code "7") (name "/GND_INDUCTED") (class "Default")
      (node (ref "L14") (pin "2") (pinfunction "2_2") (pintype "passive"))
      (node (ref "U7") (pin "3") (pinfunction "VIN_3") (pintype "passive"))
    )
    (net (code "8") (name "/HEAD_IN_A") (class "Default")
      (node (ref "R43") (pin "2") (pinfunction "2_2") (pintype "passive"))
      (node (ref "U$3") (pin "1") (pinfunction "IN_A_1") (pintype "input"))
      (node (ref "U$4") (pin "P$3") (pinfunction "P0.23_P$3") (pintype "bidirectional"))
    )
    (net (code "9") (name "/HEAD_IN_B") (class "Default")
      (node (ref "R45") (pin "2") (pinfunction "2_2") (pintype "passive"))
      (node (ref "U$3") (pin "3") (pinfunction "IN_B_3") (pintype "input"))
      (node (ref "U$4") (pin "P$4") (pinfunction "P0.24_P$4") (pintype "bidirectional"))
    )
    (net (code "10") (name "/HEAD_OUT_A") (class "Default")
      (node (ref "JP5") (pin "2") (pinfunction "2_2") (pintype "passive"))
      (node (ref "U$3") (pin "7") (pinfunction "OUT_A_7") (pintype "output"))
    )
    (net (code "11") (name "/HEAD_OUT_B") (class "Default")
      (node (ref "JP5") (pin "1") (pinfunction "1_1") (pintype "passive"))
      (node (ref "U$3") (pin "5") (pinfunction "OUT_B_5") (pintype "output"))
    )
    (net (code "12") (name "/HED_DET") (class "Default")
      (node (ref "JP1") (pin "1") (pinfunction "1_1") (pintype "passive"))
    )
    (net (code "13") (name "/HE_5V") (class "Default")
      (node (ref "JP13") (pin "5") (pinfunction "5_5") (pintype "passive"))
      (node (ref "Q6") (pin "3") (pinfunction "C_3") (pintype "passive"))
    )
    (net (code "14") (name "/H_DET") (class "Default")
      (node (ref "JP13") (pin "1") (pinfunction "1_1") (pintype "passive"))
      (node (ref "U$5") (pin "13") (pinfunction "13_13") (pintype "bidirectional"))
    )
    (net (code "15") (name "/H_L") (class "Default")
      (node (ref "JP10") (pin "2") (pinfunction "2_2") (pintype "passive"))
      (node (ref "R52") (pin "1") (pinfunction "1_1") (pintype "passive"))
    )
    (net (code "16") (name "/H_MID") (class "Default")
      (node (ref "JP10") (pin "3") (pinfunction "3_3") (pintype "passive"))
      (node (ref "R49") (pin "1") (pinfunction "1_1") (pintype "passive"))
    )
    (net (code "17") (name "/H_R") (class "Default")
      (node (ref "JP10") (pin "1") (pinfunction "1_1") (pintype "passive"))
      (node (ref "R51") (pin "1") (pinfunction "1_1") (pintype "passive"))
    )
    (net (code "18") (name "/LED_B") (class "Default")
      (node (ref "JP13") (pin "2") (pinfunction "2_2") (pintype "passive"))
      (node (ref "U$5") (pin "12") (pinfunction "12_12") (pintype "bidirectional"))
    )
    (net (code "19") (name "/LED_G") (class "Default")
      (node (ref "JP13") (pin "3") (pinfunction "3_3") (pintype "passive"))
      (node (ref "U$5") (pin "11") (pinfunction "11_11") (pintype "bidirectional"))
    )
    (net (code "20") (name "/LED_R") (class "Default")
      (node (ref "JP13") (pin "4") (pinfunction "4_4") (pintype "passive"))
      (node (ref "U$5") (pin "10") (pinfunction "10_10") (pintype "bidirectional"))
    )
    (net (code "21") (name "/LEFT_IN_A") (class "Default")
      (node (ref "R44") (pin "2") (pinfunction "2_2") (pintype "passive"))
      (node (ref "U$1") (pin "1") (pinfunction "IN_A_1") (pintype "input"))
      (node (ref "U$4") (pin "P$5") (pinfunction "P0.25_P$5") (pintype "bidirectional"))
    )
    (net (code "22") (name "/LEFT_IN_B") (class "Default")
      (node (ref "R47_OR_42") (pin "2") (pinfunction "2_2") (pintype "passive"))
      (node (ref "U$1") (pin "3") (pinfunction "IN_B_3") (pintype "input"))
      (node (ref "U$4") (pin "P$10") (pinfunction "P0.30_P$10") (pintype "bidirectional"))
    )
    (net (code "23") (name "/LEFT_OUT_A") (class "Default")
      (node (ref "JP3") (pin "2") (pinfunction "2_2") (pintype "passive"))
      (node (ref "U$1") (pin "7") (pinfunction "OUT_A_7") (pintype "output"))
    )
    (net (code "24") (name "/LEFT_OUT_B") (class "Default")
      (node (ref "JP3") (pin "1") (pinfunction "1_1") (pintype "passive"))
      (node (ref "U$1") (pin "5") (pinfunction "OUT_B_5") (pintype "output"))
    )
    (net (code "25") (name "/L_ID") (class "Default")
      (node (ref "JP8") (pin "1") (pinfunction "1_1") (pintype "passive"))
      (node (ref "R18") (pin "1") (pinfunction "1_1") (pintype "passive"))
      (node (ref "R22") (pin "1") (pinfunction "1_1") (pintype "passive"))
    )
    (net (code "26") (name "/L_LED") (class "Default")
      (node (ref "JP8") (pin "3") (pinfunction "3_3") (pintype "passive"))
      (node (ref "R6") (pin "1") (pinfunction "1_1") (pintype "passive"))
    )
    (net (code "27") (name "/MM_RESET") (class "Default")
      (node (ref "C29") (pin "2") (pinfunction "2_2") (pintype "passive"))
      (node (ref "Q12") (pin "3") (pinfunction "C_3") (pintype "passive"))
      (node (ref "U$5") (pin "5") (pinfunction "5_5") (pintype "bidirectional"))
    )
    (net (code "28") (name "/MM_RESET_OUT") (class "Default")
      (node (ref "R68") (pin "2") (pinfunction "2_2") (pintype "passive"))
      (node (ref "R71") (pin "2") (pinfunction "2_2") (pintype "passive"))
      (node (ref "U$4") (pin "P$25") (pinfunction "P0.14_P$25") (pintype "bidirectional"))
    )
    (net (code "29") (name "/OFF") (class "Default")
      (node (ref "JP9") (pin "1") (pinfunction "1_1") (pintype "passive"))
      (node (ref "R81") (pin "2") (pinfunction "2_2") (pintype "passive"))
    )
    (net (code "30") (name "/P0.15") (class "Default")
      (node (ref "U$4") (pin "P$26") (pinfunction "P0.15_P$26") (pintype "bidirectional"))
      (node (ref "U$5") (pin "18") (pinfunction "18_18") (pintype "bidirectional"))
    )
    (net (code "31") (name "/P0.17") (class "Default")
      (node (ref "U$4") (pin "P$28") (pinfunction "P0.17_P$28") (pintype "bidirectional"))
      (node (ref "U$5") (pin "20") (pinfunction "20_20") (pintype "bidirectional"))
    )
    (net (code "32") (name "/P0.18") (class "Default")
      (node (ref "U$4") (pin "P$29") (pinfunction "P0.18_P$29") (pintype "bidirectional"))
      (node (ref "U$5") (pin "21") (pinfunction "21_21") (pintype "bidirectional"))
    )
    (net (code "33") (name "/P0.19") (class "Default")
      (node (ref "U$4") (pin "P$30") (pinfunction "P0.19_P$30") (pintype "bidirectional"))
      (node (ref "U$5") (pin "22") (pinfunction "22_22") (pintype "bidirectional"))
    )
    (net (code "34") (name "/PAIR_BTN") (class "Default")
      (node (ref "JP11") (pin "1") (pinfunction "1_1") (pintype "passive"))
      (node (ref "U$4") (pin "P$24") (pinfunction "P0.13_P$24") (pintype "bidirectional"))
    )
    (net (code "35") (name "/PAIR_LED+") (class "Default")
      (node (ref "JP11") (pin "3") (pinfunction "3_3") (pintype "passive"))
      (node (ref "U$4") (pin "P$22") (pinfunction "P0.11_P$22") (pintype "bidirectional"))
    )
    (net (code "36") (name "/PAIR_LED-") (class "Default")
      (node (ref "JP11") (pin "4") (pinfunction "4_4") (pintype "passive"))
      (node (ref "R5") (pin "2") (pinfunction "2_2") (pintype "passive"))
    )
    (net (code "37") (name "/Q6_B") (class "Default")
      (node (ref "Q6") (pin "1") (pinfunction "B_1") (pintype "passive"))
      (node (ref "R27") (pin "1") (pinfunction "1_1") (pintype "passive"))
    )
    (net (code "38") (name "/Q10_B") (class "Default")
      (node (ref "Q10") (pin "1") (pinfunction "B_1") (pintype "passive"))
      (node (ref "R54") (pin "2") (pinfunction "2_2") (pintype "passive"))
      (node (ref "R60") (pin "2") (pinfunction "2_2") (pintype "passive"))
    )
    (net (code "39") (name "/Q10_C") (class "Default")
      (node (ref "Q10") (pin "3") (pinfunction "C_3") (pintype "passive"))
      (node (ref "R59") (pin "2") (pinfunction "2_2") (pintype "passive"))
    )
    (net (code "40") (name "/Q11_B") (class "Default")
      (node (ref "Q11") (pin "1") (pinfunction "B_1") (pintype "passive"))
      (node (ref "R64") (pin "1") (pinfunction "1_1") (pintype "passive"))
    )
    (net (code "41") (name "/Q11_C") (class "Default")
      (node (ref "Q11") (pin "3") (pinfunction "C_3") (pintype "passive"))
      (node (ref "R60") (pin "1") (pinfunction "1_1") (pintype "passive"))
    )
    (net (code "42") (name "/Q12_B") (class "Default")
      (node (ref "Q12") (pin "1") (pinfunction "B_1") (pintype "passive"))
      (node (ref "R68") (pin "1") (pinfunction "1_1") (pintype "passive"))
    )
    (net (code "43") (name "/Q13_B") (class "Default")
      (node (ref "Q13") (pin "1") (pinfunction "B_1") (pintype "passive"))
      (node (ref "R99") (pin "1") (pinfunction "1_1") (pintype "passive"))
    )
    (net (code "44") (name "/Q13_C") (class "Default")
      (node (ref "Q13") (pin "3") (pinfunction "C_3") (pintype "passive"))
      (node (ref "R6") (pin "2") (pinfunction "2_2") (pintype "passive"))
    )
    (net (code "45") (name "/Q14_B") (class "Default")
      (node (ref "Q14") (pin "1") (pinfunction "B_1") (pintype "passive"))
      (node (ref "R100") (pin "1") (pinfunction "1_1") (pintype "passive"))
    )
    (net (code "46") (name "/Q14_C") (class "Default")
      (node (ref "Q14") (pin "3") (pinfunction "C_3") (pintype "passive"))
      (node (ref "R7") (pin "1") (pinfunction "1_1") (pintype "passive"))
    )
    (net (code "47") (name "/R22_B") (class "Default")
      (node (ref "R22") (pin "2") (pinfunction "2_2") (pintype "passive"))
      (node (ref "U$4") (pin "P$12") (pinfunction "P0.1_P$12") (pintype "bidirectional"))
    )
    (net (code "48") (name "/R23_B") (class "Default")
      (node (ref "R18") (pin "2") (pinfunction "2_2") (pintype "passive"))
      (node (ref "R23") (pin "2") (pinfunction "2_2") (pintype "passive"))
      (node (ref "U$4") (pin "P$16") (pinfunction "P0.5_P$16") (pintype "bidirectional"))
    )
    (net (code "49") (name "/R25_B") (class "Default")
      (node (ref "R25") (pin "2") (pinfunction "2_2") (pintype "passive"))
      (node (ref "U$5") (pin "6") (pinfunction "6_6") (pintype "bidirectional"))
    )
    (net (code "50") (name "/R27_B") (class "Default")
      (node (ref "R27") (pin "2") (pinfunction "2_2") (pintype "passive"))
      (node (ref "U$5") (pin "9") (pinfunction "9_9") (pintype "bidirectional"))
    )
    (net (code "51") (name "/R29_B") (class "Default")
      (node (ref "R29") (pin "2") (pinfunction "2_2") (pintype "passive"))
      (node (ref "U$4") (pin "P$15") (pinfunction "P0.4_P$15") (pintype "bidirectional"))
    )
    (net (code "52") (name "/R49_B") (class "Default")
      (node (ref "R49") (pin "2") (pinfunction "2_2") (pintype "passive"))
      (node (ref "U$4") (pin "P$13") (pinfunction "P0.2_P$13") (pintype "bidirectional"))
    )
    (net (code "53") (name "/R51_B") (class "Default")
      (node (ref "R51") (pin "2") (pinfunction "2_2") (pintype "passive"))
      (node (ref "U$4") (pin "P$2") (pinfunction "P0.22_P$2") (pintype "bidirectional"))
    )
    (net (code "54") (name "/R52_B") (class "Default")
      (node (ref "R52") (pin "2") (pinfunction "2_2") (pintype "passive"))
      (node (ref "U$4") (pin "P$18") (pinfunction "P0.7_P$18") (pintype "bidirectional"))
    )
    (net (code "55") (name "/R55_B") (class "Default")
      (node (ref "R55") (pin "2") (pinfunction "2_2") (pintype "passive"))
      (node (ref "U$4") (pin "P$14") (pinfunction "P0.3_P$14") (pintype "bidirectional"))
    )
    (net (code "56") (name "/R61_A") (class "Default")
      (node (ref "C26") (pin "1") (pinfunction "1_1") (pintype "passive"))
      (node (ref "R55") (pin "1") (pinfunction "1_1") (pintype "passive"))
      (node (ref "R59") (pin "1") (pinfunction "1_1") (pintype "passive"))
      (node (ref "R61") (pin "1") (pinfunction "1_1") (pintype "passive"))
    )
    (net (code "57") (name "/R64_B") (class "Default")
      (node (ref "R64") (pin "2") (pinfunction "2_2") (pintype "passive"))
      (node (ref "R66") (pin "2") (pinfunction "2_2") (pintype "passive"))
      (node (ref "U$4") (pin "P$23") (pinfunction "P0.12_P$23") (pintype "bidirectional"))
    )
    (net (code "58") (name "/R99_B") (class "Default")
      (node (ref "R99") (pin "2") (pinfunction "2_2") (pintype "passive"))
      (node (ref "U$5") (pin "14") (pinfunction "14_14") (pintype "bidirectional"))
    )
    (net (code "59") (name "/R100_B") (class "Default")
      (node (ref "R100") (pin "2") (pinfunction "2_2") (pintype "passive"))
      (node (ref "U$5") (pin "15") (pinfunction "15_15") (pintype "bidirectional"))
    )
    (net (code "60") (name "/RIGHT_IN_A") (class "Default")
      (node (ref "R62") (pin "2") (pinfunction "2_2") (pintype "passive"))
      (node (ref "U$2") (pin "1") (pinfunction "IN_A_1") (pintype "input"))
      (node (ref "U$4") (pin "P$19") (pinfunction "P0.8_P$19") (pintype "bidirectional"))
    )
    (net (code "61") (name "/RIGHT_IN_B") (class "Default")
      (node (ref "R63") (pin "2") (pinfunction "2_2") (pintype "passive"))
      (node (ref "U$2") (pin "3") (pinfunction "IN_B_3") (pintype "input"))
      (node (ref "U$4") (pin "P$20") (pinfunction "P0.9_P$20") (pintype "bidirectional"))
    )
    (net (code "62") (name "/RIGHT_OUT_A") (class "Default")
      (node (ref "JP4") (pin "2") (pinfunction "2_2") (pintype "passive"))
      (node (ref "U$2") (pin "7") (pinfunction "OUT_A_7") (pintype "output"))
    )
    (net (code "63") (name "/RIGHT_OUT_B") (class "Default")
      (node (ref "JP4") (pin "1") (pinfunction "1_1") (pintype "passive"))
      (node (ref "U$2") (pin "5") (pinfunction "OUT_B_5") (pintype "output"))
    )
    (net (code "64") (name "/R_ID") (class "Default")
      (node (ref "JP7") (pin "1") (pinfunction "1_1") (pintype "passive"))
      (node (ref "R23") (pin "1") (pinfunction "1_1") (pintype "passive"))
      (node (ref "R29") (pin "1") (pinfunction "1_1") (pintype "passive"))
    )
    (net (code "65") (name "/R_LED") (class "Default")
      (node (ref "JP7") (pin "3") (pinfunction "3_3") (pintype "passive"))
      (node (ref "R7") (pin "2") (pinfunction "2_2") (pintype "passive"))
    )
    (net (code "66") (name "/SCK") (class "Default")
      (node (ref "JP14") (pin "4") (pinfunction "4_4") (pintype "passive"))
      (node (ref "JP15") (pin "2") (pinfunction "2_2") (pintype "passive"))
      (node (ref "U$5") (pin "26") (pinfunction "26_26") (pintype "bidirectional"))
    )
    (net (code "67") (name "/SCL") (class "Default")
      (node (ref "U$5") (pin "17") (pinfunction "17_17") (pintype "bidirectional"))
    )
    (net (code "68") (name "/SDA") (class "Default")
      (node (ref "JP14") (pin "3") (pinfunction "3_3") (pintype "passive"))
      (node (ref "U$5") (pin "16") (pinfunction "16_16") (pintype "bidirectional"))
    )
    (net (code "69") (name "/SI") (class "Default")
      (node (ref "JP15") (pin "5") (pinfunction "5_5") (pintype "passive"))
      (node (ref "U$5") (pin "28") (pinfunction "28_28") (pintype "bidirectional"))
    )
    (net (code "70") (name "/SICS") (class "Default")
      (node (ref "U$5") (pin "25") (pinfunction "25_25") (pintype "bidirectional"))
    )
    (net (code "71") (name "/SO") (class "Default")
      (node (ref "JP15") (pin "4") (pinfunction "4_4") (pintype "passive"))
      (node (ref "U$5") (pin "27") (pinfunction "27_27") (pintype "bidirectional"))
    )
    (net (code "72") (name "/SP+") (class "Default")
      (node (ref "L12") (pin "2") (pinfunction "2_2") (pintype "passive"))
      (node (ref "U$5") (pin "31") (pinfunction "31_31") (pintype "bidirectional"))
    )
    (net (code "73") (name "/SP+_OUT") (class "Default")
      (node (ref "C38") (pin "2") (pinfunction "2_2") (pintype "passive"))
      (node (ref "JP6") (pin "1") (pinfunction "1_1") (pintype "passive"))
      (node (ref "L12") (pin "1") (pinfunction "1_1") (pintype "passive"))
    )
    (net (code "74") (name "/SP-") (class "Default")
      (node (ref "L11") (pin "2") (pinfunction "2_2") (pintype "passive"))
      (node (ref "U$5") (pin "33") (pinfunction "33_33") (pintype "bidirectional"))
    )
    (net (code "75") (name "/SP-_OUT") (class "Default")
      (node (ref "C39") (pin "2") (pinfunction "2_2") (pintype "passive"))
      (node (ref "JP6") (pin "2") (pinfunction "2_2") (pintype "passive"))
      (node (ref "L11") (pin "1") (pinfunction "1_1") (pintype "passive"))
    )
    (net (code "76") (name "/SWCLK") (class "Default")
      (node (ref "JP12") (pin "2") (pinfunction "2_2") (pintype "passive"))
      (node (ref "U$4") (pin "P$27") (pinfunction "P0.16_P$27") (pintype "bidirectional"))
      (node (ref "U$5") (pin "19") (pinfunction "19_19") (pintype "bidirectional"))
    )
    (net (code "77") (name "/SWDIO") (class "Default")
      (node (ref "D14") (pin "A") (pinfunction "A_A") (pintype "passive"))
      (node (ref "JP12") (pin "3") (pinfunction "3_3") (pintype "passive"))
      (node (ref "U$4") (pin "P$31") (pinfunction "P0.20_P$31") (pintype "bidirectional"))
    )
    (net (code "78") (name "/U8_VIN") (class "Default")
      (node (ref "C35") (pin "2") (pinfunction "2_2") (pintype "passive"))
      (node (ref "L9") (pin "1") (pinfunction "1_1") (pintype "passive"))
      (node (ref "U8") (pin "1") (pinfunction "VSS_1") (pintype "passive"))
    )
    (net (code "79") (name "/VCC_3") (class "Default")
      (node (ref "JP1") (pin "2") (pinfunction "2_2") (pintype "passive"))
      (node (ref "JP10") (pin "4") (pinfunction "4_4") (pintype "passive"))
      (node (ref "U$4") (pin "P$11") (pinfunction "P0.00_P$11") (pintype "bidirectional"))
    )
    (net (code "80") (name "/VCC_33") (class "Default")
      (node (ref "C11") (pin "2") (pinfunction "2_2") (pintype "passive"))
      (node (ref "C31") (pin "2") (pinfunction "2_2") (pintype "passive"))
      (node (ref "JP12") (pin "4") (pinfunction "4_4") (pintype "passive"))
      (node (ref "JP15") (pin "1") (pinfunction "1_1") (pintype "passive"))
      (node (ref "U$4") (pin "P$8") (pinfunction "P0.28_P$8") (pintype "bidirectional"))
      (node (ref "U$5") (pin "2") (pinfunction "2_2") (pintype "bidirectional"))
      (node (ref "U$5") (pin "23") (pinfunction "23_23") (pintype "bidirectional"))
      (node (ref "U$5") (pin "32") (pinfunction "32_32") (pintype "bidirectional"))
      (node (ref "U$5") (pin "4") (pinfunction "4_4") (pintype "bidirectional"))
      (node (ref "U$5") (pin "7") (pinfunction "7_7") (pintype "bidirectional"))
    )
    (net (code "81") (name "/VCC_ON") (class "Default")
      (node (ref "C37") (pin "+") (pinfunction "+_+") (pintype "passive"))
      (node (ref "D14") (pin "C") (pinfunction "C_C") (pintype "passive"))
      (node (ref "JP9") (pin "2") (pinfunction "2_2") (pintype "passive"))
      (node (ref "L13") (pin "1") (pinfunction "1_1") (pintype "passive"))
    )
    (net (code "82") (name "/VCV_M") (class "Default")
      (node (ref "C16") (pin "2") (pinfunction "2_2") (pintype "passive"))
      (node (ref "C17") (pin "2") (pinfunction "2_2") (pintype "passive"))
      (node (ref "C18") (pin "2") (pinfunction "2_2") (pintype "passive"))
      (node (ref "C19") (pin "2") (pinfunction "2_2") (pintype "passive"))
      (node (ref "C27") (pin "2") (pinfunction "2_2") (pintype "passive"))
      (node (ref "C28") (pin "2") (pinfunction "2_2") (pintype "passive"))
      (node (ref "F1") (pin "P$1") (pinfunction "1_P$1") (pintype "passive"))
      (node (ref "JP9") (pin "3") (pinfunction "3_3") (pintype "passive"))
      (node (ref "U$1") (pin "4") (pinfunction "VCC_4") (pintype "power_in"))
      (node (ref "U$2") (pin "4") (pinfunction "VCC_4") (pintype "power_in"))
      (node (ref "U$3") (pin "4") (pinfunction "VCC_4") (pintype "power_in"))
    )
    (net (code "83") (name "/VPP") (class "Default")
      (node (ref "JP14") (pin "1") (pinfunction "1_1") (pintype "passive"))
      (node (ref "U$5") (pin "1") (pinfunction "1_1") (pintype "bidirectional"))
    )
    (net (code "84") (name "unconnected-(JP14-Pad5)") (class "Default")
      (node (ref "JP14") (pin "5") (pinfunction "5_5") (pintype "passive"))
    )
    (net (code "85") (name "unconnected-(U$1-NC-Pad2)") (class "Default")
      (node (ref "U$1") (pin "2") (pinfunction "NC_2") (pintype "no_connect"))
    )
    (net (code "86") (name "unconnected-(U$1-NC-Pad8)") (class "Default")
      (node (ref "U$1") (pin "8") (pinfunction "NC_8") (pintype "no_connect"))
    )
    (net (code "87") (name "unconnected-(U$2-NC-Pad2)") (class "Default")
      (node (ref "U$2") (pin "2") (pinfunction "NC_2") (pintype "no_connect"))
    )
    (net (code "88") (name "unconnected-(U$2-NC-Pad8)") (class "Default")
      (node (ref "U$2") (pin "8") (pinfunction "NC_8") (pintype "no_connect"))
    )
    (net (code "89") (name "unconnected-(U$3-NC-Pad2)") (class "Default")
      (node (ref "U$3") (pin "2") (pinfunction "NC_2") (pintype "no_connect"))
    )
    (net (code "90") (name "unconnected-(U$3-NC-Pad8)") (class "Default")
      (node (ref "U$3") (pin "8") (pinfunction "NC_8") (pintype "no_connect"))
    )
    (net (code "91") (name "unconnected-(U$4-P0.6-PadP$17)") (class "Default")
      (node (ref "U$4") (pin "P$17") (pinfunction "P0.6_P$17") (pintype "bidirectional"))
    )
    (net (code "92") (name "unconnected-(U$4-P0.10-PadP$21)") (class "Default")
      (node (ref "U$4") (pin "P$21") (pinfunction "P0.10_P$21") (pintype "bidirectional"))
    )
    (net (code "93") (name "unconnected-(U$4-P0.21-PadP$1)") (class "Default")
      (node (ref "U$4") (pin "P$1") (pinfunction "P0.21_P$1") (pintype "bidirectional"))
    )
    (net (code "94") (name "unconnected-(U$4-P0.26-PadP$6)") (class "Default")
      (node (ref "U$4") (pin "P$6") (pinfunction "P0.26_P$6") (pintype "bidirectional"))
    )
    (net (code "95") (name "unconnected-(U$4-P0.27-PadP$7)") (class "Default")
      (node (ref "U$4") (pin "P$7") (pinfunction "P0.27_P$7") (pintype "bidirectional"))
    )
  )
)
